# gyroscope-breakout.net
KiCad netlist of a schematic drawn in EAGLE
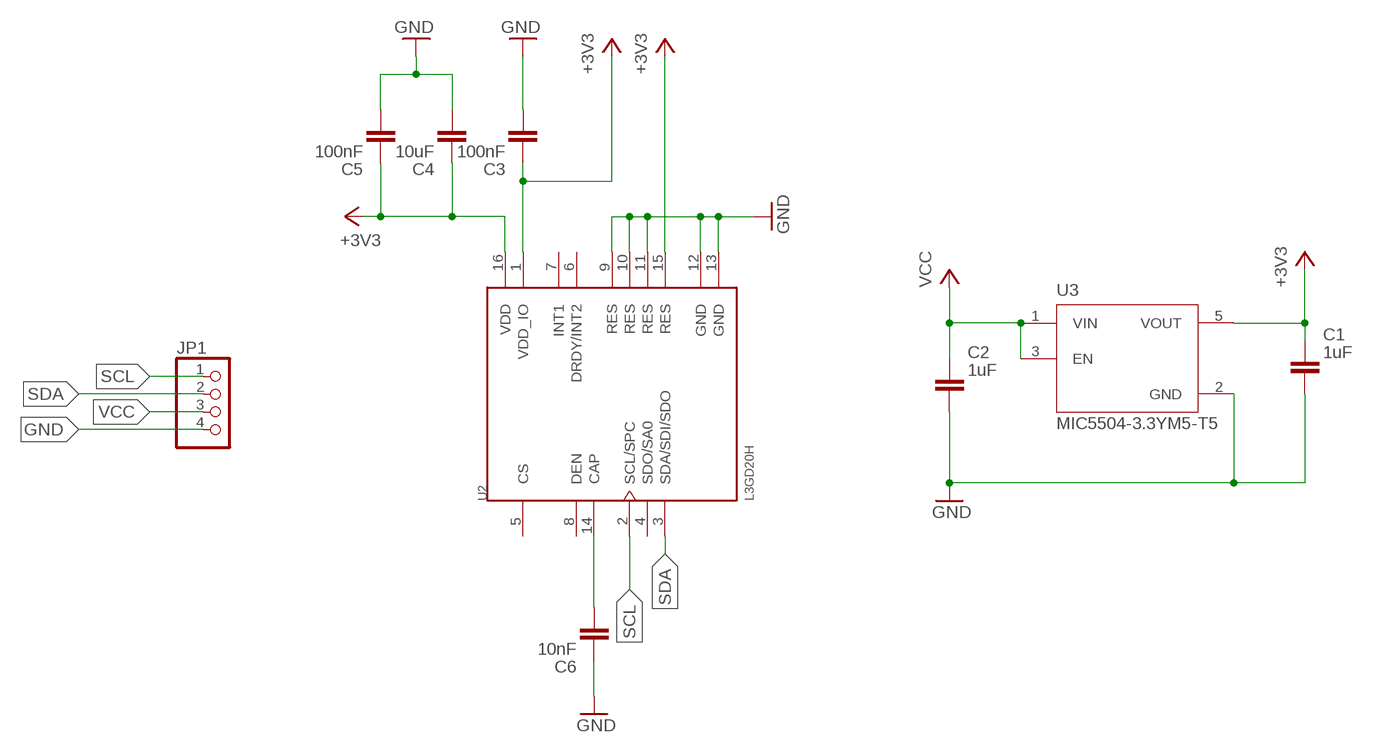
[diagram p0: schematic, sheet 1]

(export (version "E")
  (design (tool "Eeschema 10.0.6"))
  (components
    (comp (ref "C1")
      (value "1uF")
      (footprint "eagle-import:CAPC3216X135")
      (libsource (lib "eagle-import") (part "CCHIP-1206(3216-METRIC)_"))
    )
    (comp (ref "C2")
      (value "1uF")
      (footprint "eagle-import:CAPC3216X135")
      (libsource (lib "eagle-import") (part "CCHIP-1206(3216-METRIC)_"))
    )
    (comp (ref "C3")
      (value "100nF")
      (footprint "eagle-import:CAPC3216X135")
      (libsource (lib "eagle-import") (part "CCHIP-1206(3216-METRIC)_"))
    )
    (comp (ref "C4")
      (value "10uF")
      (footprint "eagle-import:CAPC3216X135")
      (libsource (lib "eagle-import") (part "CCHIP-1206(3216-METRIC)_"))
    )
    (comp (ref "C5")
      (value "100nF")
      (footprint "eagle-import:CAPC3216X135")
      (libsource (lib "eagle-import") (part "CCHIP-1206(3216-METRIC)_"))
    )
    (comp (ref "C6")
      (value "10nF")
      (footprint "eagle-import:CAPC3216X135")
      (libsource (lib "eagle-import") (part "CCHIP-1206(3216-METRIC)_"))
    )
    (comp (ref "JP1")
      (value "PINHD-1X4")
      (footprint "eagle-import:1X04")
      (libsource (lib "eagle-import") (part "PINHD-1X4"))
    )
    (comp (ref "U2")
      (value "L3GD20H")
      (footprint "eagle-import:LGA16R50P7X5_300X300X100")
      (fields (field (name "MF") "STMicroelectronics"))
      (libsource (lib "eagle-import") (part "L3GD20H"))
    )
    (comp (ref "U3")
      (value "MIC5504-3.3YM5-T5")
      (footprint "eagle-import:SOT95P280X145-5N")
      (fields (field (name "MF") "Microchip"))
      (libsource (lib "eagle-import") (part "MIC5504-3.3YM5-T5"))
    )
  )
  (nets
    (net (code "1") (name "+3V3") (class "Default")
      (node (ref "C1") (pin "1") (pinfunction "1_1") (pintype "passive"))
      (node (ref "C3") (pin "1") (pinfunction "1_1") (pintype "passive"))
      (node (ref "C4") (pin "1") (pinfunction "1_1") (pintype "passive"))
      (node (ref "C5") (pin "1") (pinfunction "1_1") (pintype "passive"))
      (node (ref "U2") (pin "1") (pinfunction "VDD_IO_1") (pintype "power_in"))
      (node (ref "U2") (pin "15") (pinfunction "RES_15") (pintype "power_in"))
      (node (ref "U2") (pin "16") (pinfunction "VDD_16") (pintype "power_in"))
      (node (ref "U3") (pin "5") (pinfunction "VOUT_5") (pintype "output"))
    )
    (net (code "2") (name "GND") (class "Default")
      (node (ref "C1") (pin "2") (pinfunction "2_2") (pintype "passive"))
      (node (ref "C2") (pin "2") (pinfunction "2_2") (pintype "passive"))
      (node (ref "C3") (pin "2") (pinfunction "2_2") (pintype "passive"))
      (node (ref "C4") (pin "2") (pinfunction "2_2") (pintype "passive"))
      (node (ref "C5") (pin "2") (pinfunction "2_2") (pintype "passive"))
      (node (ref "C6") (pin "1") (pinfunction "1_1") (pintype "passive"))
      (node (ref "JP1") (pin "4") (pinfunction "4_4") (pintype "passive"))
      (node (ref "U2") (pin "10") (pinfunction "RES_10") (pintype "power_in"))
      (node (ref "U2") (pin "11") (pinfunction "RES_11") (pintype "power_in"))
      (node (ref "U2") (pin "12") (pinfunction "GND_12") (pintype "power_in"))
      (node (ref "U2") (pin "13") (pinfunction "GND_13") (pintype "power_in"))
      (node (ref "U2") (pin "9") (pinfunction "RES_9") (pintype "power_in"))
      (node (ref "U3") (pin "2") (pinfunction "GND_2") (pintype "power_in"))
    )
    (net (code "3") (name "Net-(U2-CAP)") (class "Default")
      (node (ref "C6") (pin "2") (pinfunction "2_2") (pintype "passive"))
      (node (ref "U2") (pin "14") (pinfunction "CAP_14") (pintype "passive"))
    )
    (net (code "4") (name "SCL") (class "Default")
      (node (ref "JP1") (pin "1") (pinfunction "1_1") (pintype "passive"))
      (node (ref "U2") (pin "2") (pinfunction "SCL/SPC_2") (pintype "input"))
    )
    (net (code "5") (name "SDA") (class "Default")
      (node (ref "JP1") (pin "2") (pinfunction "2_2") (pintype "passive"))
      (node (ref "U2") (pin "3") (pinfunction "SDA/SDI/SDO_3") (pintype "bidirectional"))
    )
    (net (code "6") (name "VCC") (class "Default")
      (node (ref "C2") (pin "1") (pinfunction "1_1") (pintype "passive"))
      (node (ref "JP1") (pin "3") (pinfunction "3_3") (pintype "passive"))
      (node (ref "U3") (pin "1") (pinfunction "VIN_1") (pintype "input"))
      (node (ref "U3") (pin "3") (pinfunction "EN_3") (pintype "input"))
    )
    (net (code "7") (name "unconnected-(U2-CS-Pad5)") (class "Default")
      (node (ref "U2") (pin "5") (pinfunction "CS_5") (pintype "input"))
    )
    (net (code "8") (name "unconnected-(U2-DEN-Pad8)") (class "Default")
      (node (ref "U2") (pin "8") (pinfunction "DEN_8") (pintype "input"))
    )
    (net (code "9") (name "unconnected-(U2-DRDY{slash}INT2-Pad6)") (class "Default")
      (node (ref "U2") (pin "6") (pinfunction "DRDY/INT2_6") (pintype "output"))
    )
    (net (code "10") (name "unconnected-(U2-INT1-Pad7)") (class "Default")
      (node (ref "U2") (pin "7") (pinfunction "INT1_7") (pintype "output"))
    )
    (net (code "11") (name "unconnected-(U2-SDO{slash}SA0-Pad4)") (class "Default")
      (node (ref "U2") (pin "4") (pinfunction "SDO/SA0_4") (pintype "bidirectional"))
    )
  )
)
